# Sheet1.net
KiCad netlist of a schematic drawn in Altium Designer
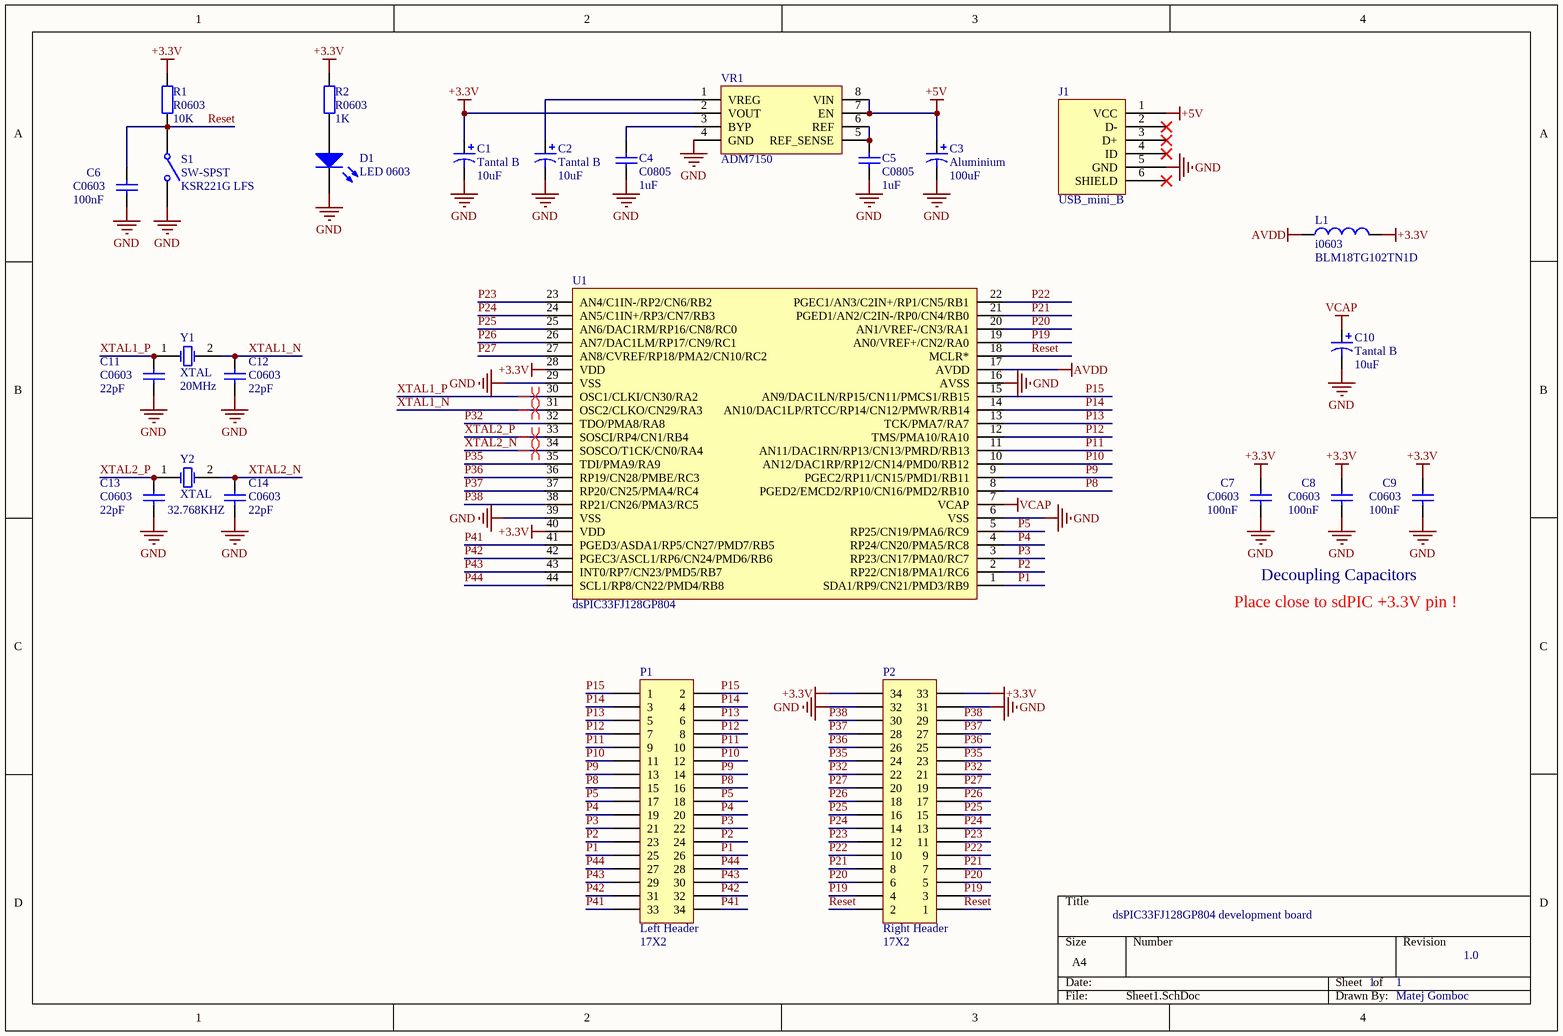
[diagram p0: Sheet1.SchDoc]

(export (version "E")
  (design (tool "Eeschema 10.0.6"))
  (components
    (comp (ref "C1")
      (value "Tantal B")
      (footprint "AVX-CAPC3528_V")
      (description "Tantalum Capacitor")
      (fields (field (name "ALTIUM_VALUE") "10uF"))
      (libsource (lib "Miscellaneous Devices Local Copy") (part "Cap Pol1"))
    )
    (comp (ref "C2")
      (value "Tantal B")
      (footprint "AVX-CAPC3528_V")
      (description "Tantalum Capacitor")
      (fields (field (name "ALTIUM_VALUE") "10uF"))
      (libsource (lib "Miscellaneous Devices Local Copy") (part "Cap Pol1"))
    )
    (comp (ref "C3")
      (value "Aluminium")
      (footprint "Panasonic Size D8")
      (description "Aluminium Capacitor")
      (fields (field (name "ALTIUM_VALUE") "100uF"))
      (libsource (lib "Miscellaneous Devices Local Copy") (part "Cap Pol1"))
    )
    (comp (ref "C4")
      (value "C0805")
      (footprint "C0805")
      (description "Ceramic Capacitor")
      (fields (field (name "ALTIUM_VALUE") "1uF"))
      (libsource (lib "Miscellaneous Devices Local Copy") (part "Cap"))
    )
    (comp (ref "C5")
      (value "C0805")
      (footprint "C0805")
      (description "Ceramic Capacitor")
      (fields (field (name "ALTIUM_VALUE") "1uF"))
      (libsource (lib "Miscellaneous Devices Local Copy") (part "Cap"))
    )
    (comp (ref "C6")
      (value "C0603")
      (footprint "0603_HandSoldering")
      (description "Ceramic Capacitor")
      (fields (field (name "ALTIUM_VALUE") "100nF"))
      (libsource (lib "Miscellaneous Devices Local Copy") (part "Cap"))
    )
    (comp (ref "C7")
      (value "C0603")
      (footprint "0603_HandSoldering")
      (description "Ceramic Capacitor")
      (fields (field (name "ALTIUM_VALUE") "100nF"))
      (libsource (lib "Miscellaneous Devices Local Copy") (part "Cap"))
    )
    (comp (ref "C8")
      (value "C0603")
      (footprint "0603_HandSoldering")
      (description "Ceramic Capacitor")
      (fields (field (name "ALTIUM_VALUE") "100nF"))
      (libsource (lib "Miscellaneous Devices Local Copy") (part "Cap"))
    )
    (comp (ref "C9")
      (value "C0603")
      (footprint "0603_HandSoldering")
      (description "Ceramic Capacitor")
      (fields (field (name "ALTIUM_VALUE") "100nF"))
      (libsource (lib "Miscellaneous Devices Local Copy") (part "Cap"))
    )
    (comp (ref "C10")
      (value "Tantal B")
      (footprint "AVX-CAPC3528_V")
      (description "Tantalum Capacitor")
      (fields (field (name "ALTIUM_VALUE") "10uF"))
      (libsource (lib "Miscellaneous Devices Local Copy") (part "Cap Pol1"))
    )
    (comp (ref "C11")
      (value "C0603")
      (footprint "0603_HandSoldering")
      (description "Ceramic Capacitor")
      (fields (field (name "ALTIUM_VALUE") "22pF"))
      (libsource (lib "Miscellaneous Devices Local Copy") (part "Cap"))
    )
    (comp (ref "C12")
      (value "C0603")
      (footprint "0603_HandSoldering")
      (description "Ceramic Capacitor")
      (fields (field (name "ALTIUM_VALUE") "22pF"))
      (libsource (lib "Miscellaneous Devices Local Copy") (part "Cap"))
    )
    (comp (ref "C13")
      (value "C0603")
      (footprint "0603_HandSoldering")
      (description "Ceramic Capacitor")
      (fields (field (name "ALTIUM_VALUE") "22pF"))
      (libsource (lib "Miscellaneous Devices Local Copy") (part "Cap"))
    )
    (comp (ref "C14")
      (value "C0603")
      (footprint "0603_HandSoldering")
      (description "Ceramic Capacitor")
      (fields (field (name "ALTIUM_VALUE") "22pF"))
      (libsource (lib "Miscellaneous Devices Local Copy") (part "Cap"))
    )
    (comp (ref "D1")
      (value "LED 0603")
      (footprint "0603_LED")
      (description "SMD LED 0603")
      (libsource (lib "Miscellaneous Devices Local Copy") (part "LED2"))
    )
    (comp (ref "J1")
      (value "USB_mini_B")
      (footprint "USB mini B receptacle")
      (description "USB 2.0 mini B receptacle")
      (libsource (lib "IntegratedSchlib") (part "USB_mini_B"))
    )
    (comp (ref "L1")
      (value "i0603")
      (footprint "0603_HandSoldering")
      (description "Inductor")
      (fields (field (name "ALTIUM_VALUE") "BLM18TG102TN1D"))
      (libsource (lib "Miscellaneous Devices Local Copy") (part "Inductor"))
    )
    (comp (ref "P1")
      (value "Left Header")
      (footprint "HDR2X17")
      (description "Header, 17-Pin, Dual row")
      (fields (field (name "ALTIUM_VALUE") "17X2"))
      (libsource (lib "") (part "Header 17X2_1"))
    )
    (comp (ref "P2")
      (value "Right Header")
      (footprint "HDR2X17")
      (description "Header, 17-Pin, Dual row")
      (fields (field (name "ALTIUM_VALUE") "17X2"))
      (libsource (lib "Miscellaneous Connectors Local Copy") (part "Header 17X2"))
    )
    (comp (ref "R1")
      (value "R0603")
      (footprint "0603_HandSoldering")
      (description "Resistor")
      (fields (field (name "ALTIUM_VALUE") "10K"))
      (libsource (lib "Miscellaneous Devices Local Copy") (part "Res2"))
    )
    (comp (ref "R2")
      (value "R0603")
      (footprint "0603_HandSoldering")
      (description "Resistor")
      (fields (field (name "ALTIUM_VALUE") "1K"))
      (libsource (lib "Miscellaneous Devices Local Copy") (part "Res2"))
    )
    (comp (ref "S1")
      (value "SW-SPST")
      (footprint "KSR221G_LFS_Tactile_Switch")
      (description "KSR221G LFS Tactile Switch")
      (fields (field (name "ALTIUM_VALUE") "KSR221G LFS"))
      (libsource (lib "Miscellaneous Devices Local Copy") (part "SW-SPST"))
    )
    (comp (ref "U1")
      (value "dsPIC33FJ128GP804")
      (footprint "dsPIC33FJ128GP804_TQFP44")
      (description "dsPIC 40 MIPS")
      (libsource (lib "IntegratedSchlib") (part "dsPIC33FJ128GP804"))
    )
    (comp (ref "VR1")
      (value "ADM7150")
      (footprint "ADM7150_SOIC8")
      (description "800 mA Ultralow Noise,  High PSRR, RF Linear Regulator")
      (libsource (lib "IntegratedSchlib") (part "ADM7150"))
    )
    (comp (ref "Y1")
      (value "XTAL")
      (footprint "TXC  7A-20.000MAAJ-T  XTAL")
      (description "TXC  7A-20.000MAAJ-T  XTAL")
      (fields (field (name "ALTIUM_VALUE") "20MHz"))
      (libsource (lib "Miscellaneous Devices Local Copy") (part "XTAL"))
    )
    (comp (ref "Y2")
      (value "XTAL")
      (footprint "Raltron R26-32.768- 12.5  CRYSTAL")
      (description "RALTRON  R26-32.768- 12.5  CRYSTAL")
      (fields (field (name "ALTIUM_VALUE") "32.768KHZ"))
      (libsource (lib "Miscellaneous Devices Local Copy") (part "XTAL"))
    )
  )
  (nets
    (net (code "1") (name "+3.3V") (class "Default")
      (node (ref "C1") (pin "1") (pinfunction "1_1") (pintype "passive"))
      (node (ref "C7") (pin "2") (pinfunction "2_2") (pintype "passive"))
      (node (ref "C8") (pin "2") (pinfunction "2_2") (pintype "passive"))
      (node (ref "C9") (pin "2") (pinfunction "2_2") (pintype "passive"))
      (node (ref "L1") (pin "2") (pinfunction "2_2") (pintype "passive"))
      (node (ref "P2") (pin "33") (pinfunction "33_33") (pintype "passive"))
      (node (ref "P2") (pin "34") (pinfunction "34_34") (pintype "passive"))
      (node (ref "R1") (pin "2") (pinfunction "2_2") (pintype "passive"))
      (node (ref "R2") (pin "2") (pinfunction "2_2") (pintype "passive"))
      (node (ref "U1") (pin "28") (pinfunction "VDD_28") (pintype "passive"))
      (node (ref "U1") (pin "40") (pinfunction "VDD_40") (pintype "passive"))
      (node (ref "VR1") (pin "2") (pinfunction "VOUT_2") (pintype "passive"))
    )
    (net (code "2") (name "+5V") (class "Default")
      (node (ref "C3") (pin "1") (pinfunction "1_1") (pintype "passive"))
      (node (ref "J1") (pin "1") (pinfunction "VCC_1") (pintype "passive"))
      (node (ref "VR1") (pin "7") (pinfunction "EN_7") (pintype "passive"))
      (node (ref "VR1") (pin "8") (pinfunction "VIN_8") (pintype "passive"))
    )
    (net (code "3") (name "/P1") (class "Default")
      (node (ref "P1") (pin "25") (pinfunction "25_25") (pintype "passive"))
      (node (ref "P1") (pin "26") (pinfunction "26_26") (pintype "passive"))
      (node (ref "U1") (pin "1") (pinfunction "SDA1/RP9/CN21/PMD3/RB9_1") (pintype "passive"))
    )
    (net (code "4") (name "/P2") (class "Default")
      (node (ref "P1") (pin "23") (pinfunction "23_23") (pintype "passive"))
      (node (ref "P1") (pin "24") (pinfunction "24_24") (pintype "passive"))
      (node (ref "U1") (pin "2") (pinfunction "RP22/CN18/PMA1/RC6_2") (pintype "passive"))
    )
    (net (code "5") (name "/P3") (class "Default")
      (node (ref "P1") (pin "21") (pinfunction "21_21") (pintype "passive"))
      (node (ref "P1") (pin "22") (pinfunction "22_22") (pintype "passive"))
      (node (ref "U1") (pin "3") (pinfunction "RP23/CN17/PMA0/RC7_3") (pintype "passive"))
    )
    (net (code "6") (name "/P4") (class "Default")
      (node (ref "P1") (pin "19") (pinfunction "19_19") (pintype "passive"))
      (node (ref "P1") (pin "20") (pinfunction "20_20") (pintype "passive"))
      (node (ref "U1") (pin "4") (pinfunction "RP24/CN20/PMA5/RC8_4") (pintype "passive"))
    )
    (net (code "7") (name "/P5") (class "Default")
      (node (ref "P1") (pin "17") (pinfunction "17_17") (pintype "passive"))
      (node (ref "P1") (pin "18") (pinfunction "18_18") (pintype "passive"))
      (node (ref "U1") (pin "5") (pinfunction "RP25/CN19/PMA6/RC9_5") (pintype "passive"))
    )
    (net (code "8") (name "/P8") (class "Default")
      (node (ref "P1") (pin "15") (pinfunction "15_15") (pintype "passive"))
      (node (ref "P1") (pin "16") (pinfunction "16_16") (pintype "passive"))
      (node (ref "U1") (pin "8") (pinfunction "PGED2/EMCD2/RP10/CN16/PMD2/RB10_8") (pintype "passive"))
    )
    (net (code "9") (name "/P9") (class "Default")
      (node (ref "P1") (pin "13") (pinfunction "13_13") (pintype "passive"))
      (node (ref "P1") (pin "14") (pinfunction "14_14") (pintype "passive"))
      (node (ref "U1") (pin "9") (pinfunction "PGEC2/RP11/CN15/PMD1/RB11_9") (pintype "passive"))
    )
    (net (code "10") (name "/P10") (class "Default")
      (node (ref "P1") (pin "11") (pinfunction "11_11") (pintype "passive"))
      (node (ref "P1") (pin "12") (pinfunction "12_12") (pintype "passive"))
      (node (ref "U1") (pin "10") (pinfunction "AN12/DAC1RP/RP12/CN14/PMD0/RB12_10") (pintype "passive"))
    )
    (net (code "11") (name "/P11") (class "Default")
      (node (ref "P1") (pin "10") (pinfunction "10_10") (pintype "passive"))
      (node (ref "P1") (pin "9") (pinfunction "9_9") (pintype "passive"))
      (node (ref "U1") (pin "11") (pinfunction "AN11/DAC1RN/RP13/CN13/PMRD/RB13_11") (pintype "passive"))
    )
    (net (code "12") (name "/P12") (class "Default")
      (node (ref "P1") (pin "7") (pinfunction "7_7") (pintype "passive"))
      (node (ref "P1") (pin "8") (pinfunction "8_8") (pintype "passive"))
      (node (ref "U1") (pin "12") (pinfunction "TMS/PMA10/RA10_12") (pintype "passive"))
    )
    (net (code "13") (name "/P13") (class "Default")
      (node (ref "P1") (pin "5") (pinfunction "5_5") (pintype "passive"))
      (node (ref "P1") (pin "6") (pinfunction "6_6") (pintype "passive"))
      (node (ref "U1") (pin "13") (pinfunction "TCK/PMA7/RA7_13") (pintype "passive"))
    )
    (net (code "14") (name "/P14") (class "Default")
      (node (ref "P1") (pin "3") (pinfunction "3_3") (pintype "passive"))
      (node (ref "P1") (pin "4") (pinfunction "4_4") (pintype "passive"))
      (node (ref "U1") (pin "14") (pinfunction "AN10/DAC1LP/RTCC/RP14/CN12/PMWR/RB14_14") (pintype "passive"))
    )
    (net (code "15") (name "/P15") (class "Default")
      (node (ref "P1") (pin "1") (pinfunction "1_1") (pintype "passive"))
      (node (ref "P1") (pin "2") (pinfunction "2_2") (pintype "passive"))
      (node (ref "U1") (pin "15") (pinfunction "AN9/DAC1LN/RP15/CN11/PMCS1/RB15_15") (pintype "passive"))
    )
    (net (code "16") (name "/P19") (class "Default")
      (node (ref "P2") (pin "3") (pinfunction "3_3") (pintype "passive"))
      (node (ref "P2") (pin "4") (pinfunction "4_4") (pintype "passive"))
      (node (ref "U1") (pin "19") (pinfunction "AN0/VREF+/CN2/RA0_19") (pintype "passive"))
    )
    (net (code "17") (name "/P20") (class "Default")
      (node (ref "P2") (pin "5") (pinfunction "5_5") (pintype "passive"))
      (node (ref "P2") (pin "6") (pinfunction "6_6") (pintype "passive"))
      (node (ref "U1") (pin "20") (pinfunction "AN1/VREF-/CN3/RA1_20") (pintype "passive"))
    )
    (net (code "18") (name "/P21") (class "Default")
      (node (ref "P2") (pin "7") (pinfunction "7_7") (pintype "passive"))
      (node (ref "P2") (pin "8") (pinfunction "8_8") (pintype "passive"))
      (node (ref "U1") (pin "21") (pinfunction "PGED1/AN2/C2IN-/RP0/CN4/RB0_21") (pintype "passive"))
    )
    (net (code "19") (name "/P22") (class "Default")
      (node (ref "P2") (pin "10") (pinfunction "10_10") (pintype "passive"))
      (node (ref "P2") (pin "9") (pinfunction "9_9") (pintype "passive"))
      (node (ref "U1") (pin "22") (pinfunction "PGEC1/AN3/C2IN+/RP1/CN5/RB1_22") (pintype "passive"))
    )
    (net (code "20") (name "/P23") (class "Default")
      (node (ref "P2") (pin "11") (pinfunction "11_11") (pintype "passive"))
      (node (ref "P2") (pin "12") (pinfunction "12_12") (pintype "passive"))
      (node (ref "U1") (pin "23") (pinfunction "AN4/C1IN-/RP2/CN6/RB2_23") (pintype "passive"))
    )
    (net (code "21") (name "/P24") (class "Default")
      (node (ref "P2") (pin "13") (pinfunction "13_13") (pintype "passive"))
      (node (ref "P2") (pin "14") (pinfunction "14_14") (pintype "passive"))
      (node (ref "U1") (pin "24") (pinfunction "AN5/C1IN+/RP3/CN7/RB3_24") (pintype "passive"))
    )
    (net (code "22") (name "/P25") (class "Default")
      (node (ref "P2") (pin "15") (pinfunction "15_15") (pintype "passive"))
      (node (ref "P2") (pin "16") (pinfunction "16_16") (pintype "passive"))
      (node (ref "U1") (pin "25") (pinfunction "AN6/DAC1RM/RP16/CN8/RC0_25") (pintype "passive"))
    )
    (net (code "23") (name "/P26") (class "Default")
      (node (ref "P2") (pin "17") (pinfunction "17_17") (pintype "passive"))
      (node (ref "P2") (pin "18") (pinfunction "18_18") (pintype "passive"))
      (node (ref "U1") (pin "26") (pinfunction "AN7/DAC1LM/RP17/CN9/RC1_26") (pintype "passive"))
    )
    (net (code "24") (name "/P27") (class "Default")
      (node (ref "P2") (pin "19") (pinfunction "19_19") (pintype "passive"))
      (node (ref "P2") (pin "20") (pinfunction "20_20") (pintype "passive"))
      (node (ref "U1") (pin "27") (pinfunction "AN8/CVREF/RP18/PMA2/CN10/RC2_27") (pintype "passive"))
    )
    (net (code "25") (name "/P32") (class "Default")
      (node (ref "P2") (pin "21") (pinfunction "21_21") (pintype "passive"))
      (node (ref "P2") (pin "22") (pinfunction "22_22") (pintype "passive"))
      (node (ref "U1") (pin "32") (pinfunction "TDO/PMA8/RA8_32") (pintype "passive"))
    )
    (net (code "26") (name "/P35") (class "Default")
      (node (ref "P2") (pin "23") (pinfunction "23_23") (pintype "passive"))
      (node (ref "P2") (pin "24") (pinfunction "24_24") (pintype "passive"))
      (node (ref "U1") (pin "35") (pinfunction "TDI/PMA9/RA9_35") (pintype "passive"))
    )
    (net (code "27") (name "/P36") (class "Default")
      (node (ref "P2") (pin "25") (pinfunction "25_25") (pintype "passive"))
      (node (ref "P2") (pin "26") (pinfunction "26_26") (pintype "passive"))
      (node (ref "U1") (pin "36") (pinfunction "RP19/CN28/PMBE/RC3_36") (pintype "passive"))
    )
    (net (code "28") (name "/P37") (class "Default")
      (node (ref "P2") (pin "27") (pinfunction "27_27") (pintype "passive"))
      (node (ref "P2") (pin "28") (pinfunction "28_28") (pintype "passive"))
      (node (ref "U1") (pin "37") (pinfunction "RP20/CN25/PMA4/RC4_37") (pintype "passive"))
    )
    (net (code "29") (name "/P38") (class "Default")
      (node (ref "P2") (pin "29") (pinfunction "29_29") (pintype "passive"))
      (node (ref "P2") (pin "30") (pinfunction "30_30") (pintype "passive"))
      (node (ref "U1") (pin "38") (pinfunction "RP21/CN26/PMA3/RC5_38") (pintype "passive"))
    )
    (net (code "30") (name "/P41") (class "Default")
      (node (ref "P1") (pin "33") (pinfunction "33_33") (pintype "passive"))
      (node (ref "P1") (pin "34") (pinfunction "34_34") (pintype "passive"))
      (node (ref "U1") (pin "41") (pinfunction "PGED3/ASDA1/RP5/CN27/PMD7/RB5_41") (pintype "passive"))
    )
    (net (code "31") (name "/P42") (class "Default")
      (node (ref "P1") (pin "31") (pinfunction "31_31") (pintype "passive"))
      (node (ref "P1") (pin "32") (pinfunction "32_32") (pintype "passive"))
      (node (ref "U1") (pin "42") (pinfunction "PGEC3/ASCL1/RP6/CN24/PMD6/RB6_42") (pintype "passive"))
    )
    (net (code "32") (name "/P43") (class "Default")
      (node (ref "P1") (pin "29") (pinfunction "29_29") (pintype "passive"))
      (node (ref "P1") (pin "30") (pinfunction "30_30") (pintype "passive"))
      (node (ref "U1") (pin "43") (pinfunction "INT0/RP7/CN23/PMD5/RB7_43") (pintype "passive"))
    )
    (net (code "33") (name "/P44") (class "Default")
      (node (ref "P1") (pin "27") (pinfunction "27_27") (pintype "passive"))
      (node (ref "P1") (pin "28") (pinfunction "28_28") (pintype "passive"))
      (node (ref "U1") (pin "44") (pinfunction "SCL1/RP8/CN22/PMD4/RB8_44") (pintype "passive"))
    )
    (net (code "34") (name "/Reset") (class "Default")
      (node (ref "C6") (pin "2") (pinfunction "2_2") (pintype "passive"))
      (node (ref "P2") (pin "1") (pinfunction "1_1") (pintype "passive"))
      (node (ref "P2") (pin "2") (pinfunction "2_2") (pintype "passive"))
      (node (ref "R1") (pin "1") (pinfunction "1_1") (pintype "passive"))
      (node (ref "S1") (pin "1") (pinfunction "COMMON_1") (pintype "passive"))
      (node (ref "U1") (pin "18") (pinfunction "MCLR*_18") (pintype "passive"))
    )
    (net (code "35") (name "/XTAL1_N") (class "Default")
      (node (ref "C12") (pin "2") (pinfunction "2_2") (pintype "passive"))
      (node (ref "U1") (pin "31") (pinfunction "OSC2/CLKO/CN29/RA3_31") (pintype "passive"))
      (node (ref "Y1") (pin "2") (pinfunction "OSC2_2") (pintype "passive"))
    )
    (net (code "36") (name "/XTAL1_P") (class "Default")
      (node (ref "C11") (pin "2") (pinfunction "2_2") (pintype "passive"))
      (node (ref "U1") (pin "30") (pinfunction "OSC1/CLKI/CN30/RA2_30") (pintype "passive"))
      (node (ref "Y1") (pin "1") (pinfunction "OSC1_1") (pintype "passive"))
    )
    (net (code "37") (name "/XTAL2_N") (class "Default")
      (node (ref "C14") (pin "2") (pinfunction "2_2") (pintype "passive"))
      (node (ref "U1") (pin "34") (pinfunction "SOSCO/T1CK/CN0/RA4_34") (pintype "passive"))
      (node (ref "Y2") (pin "2") (pinfunction "OSC2_2") (pintype "passive"))
    )
    (net (code "38") (name "/XTAL2_P") (class "Default")
      (node (ref "C13") (pin "2") (pinfunction "2_2") (pintype "passive"))
      (node (ref "U1") (pin "33") (pinfunction "SOSCI/RP4/CN1/RB4_33") (pintype "passive"))
      (node (ref "Y2") (pin "1") (pinfunction "OSC1_1") (pintype "passive"))
    )
    (net (code "39") (name "AVDD") (class "Default")
      (node (ref "L1") (pin "1") (pinfunction "1_1") (pintype "passive"))
      (node (ref "U1") (pin "17") (pinfunction "AVDD_17") (pintype "passive"))
    )
    (net (code "40") (name "GND") (class "Default")
      (node (ref "C1") (pin "2") (pinfunction "2_2") (pintype "passive"))
      (node (ref "C10") (pin "2") (pinfunction "2_2") (pintype "passive"))
      (node (ref "C11") (pin "1") (pinfunction "1_1") (pintype "passive"))
      (node (ref "C12") (pin "1") (pinfunction "1_1") (pintype "passive"))
      (node (ref "C13") (pin "1") (pinfunction "1_1") (pintype "passive"))
      (node (ref "C14") (pin "1") (pinfunction "1_1") (pintype "passive"))
      (node (ref "C2") (pin "2") (pinfunction "2_2") (pintype "passive"))
      (node (ref "C3") (pin "2") (pinfunction "2_2") (pintype "passive"))
      (node (ref "C4") (pin "1") (pinfunction "1_1") (pintype "passive"))
      (node (ref "C5") (pin "1") (pinfunction "1_1") (pintype "passive"))
      (node (ref "C6") (pin "1") (pinfunction "1_1") (pintype "passive"))
      (node (ref "C7") (pin "1") (pinfunction "1_1") (pintype "passive"))
      (node (ref "C8") (pin "1") (pinfunction "1_1") (pintype "passive"))
      (node (ref "C9") (pin "1") (pinfunction "1_1") (pintype "passive"))
      (node (ref "D1") (pin "2") (pinfunction "K_2") (pintype "passive"))
      (node (ref "J1") (pin "5") (pinfunction "GND_5") (pintype "passive"))
      (node (ref "P2") (pin "31") (pinfunction "31_31") (pintype "passive"))
      (node (ref "P2") (pin "32") (pinfunction "32_32") (pintype "passive"))
      (node (ref "S1") (pin "2") (pinfunction "NO_2") (pintype "passive"))
      (node (ref "U1") (pin "16") (pinfunction "AVSS_16") (pintype "passive"))
      (node (ref "U1") (pin "29") (pinfunction "VSS_29") (pintype "passive"))
      (node (ref "U1") (pin "39") (pinfunction "VSS_39") (pintype "passive"))
      (node (ref "U1") (pin "6") (pinfunction "VSS_6") (pintype "passive"))
      (node (ref "VR1") (pin "4") (pinfunction "GND_4") (pintype "passive"))
    )
    (net (code "41") (name "Net-(D1-A)") (class "Default")
      (node (ref "D1") (pin "1") (pinfunction "A_1") (pintype "passive"))
      (node (ref "R2") (pin "1") (pinfunction "1_1") (pintype "passive"))
    )
    (net (code "42") (name "Net-(VR1-BYP)") (class "Default")
      (node (ref "C4") (pin "2") (pinfunction "2_2") (pintype "passive"))
      (node (ref "VR1") (pin "3") (pinfunction "BYP_3") (pintype "passive"))
    )
    (net (code "43") (name "Net-(VR1-REF)") (class "Default")
      (node (ref "C5") (pin "2") (pinfunction "2_2") (pintype "passive"))
      (node (ref "VR1") (pin "5") (pinfunction "REF_SENSE_5") (pintype "passive"))
      (node (ref "VR1") (pin "6") (pinfunction "REF_6") (pintype "passive"))
    )
    (net (code "44") (name "Net-(VR1-VREG)") (class "Default")
      (node (ref "C2") (pin "1") (pinfunction "1_1") (pintype "passive"))
      (node (ref "VR1") (pin "1") (pinfunction "VREG_1") (pintype "passive"))
    )
    (net (code "45") (name "VCAP") (class "Default")
      (node (ref "C10") (pin "1") (pinfunction "1_1") (pintype "passive"))
      (node (ref "U1") (pin "7") (pinfunction "VCAP_7") (pintype "passive"))
    )
    (net (code "46") (name "unconnected-(J1-D+-Pad3)") (class "Default")
      (node (ref "J1") (pin "3") (pinfunction "D+_3") (pintype "passive+no_connect"))
    )
    (net (code "47") (name "unconnected-(J1-D--Pad2)") (class "Default")
      (node (ref "J1") (pin "2") (pinfunction "D-_2") (pintype "passive+no_connect"))
    )
    (net (code "48") (name "unconnected-(J1-ID-Pad4)") (class "Default")
      (node (ref "J1") (pin "4") (pinfunction "ID_4") (pintype "passive+no_connect"))
    )
    (net (code "49") (name "unconnected-(J1-SHIELD-Pad6)") (class "Default")
      (node (ref "J1") (pin "6") (pinfunction "SHIELD_6") (pintype "passive+no_connect"))
    )
  )
)
